# Ethernet.net
KiCad netlist of a schematic drawn in Altium Designer
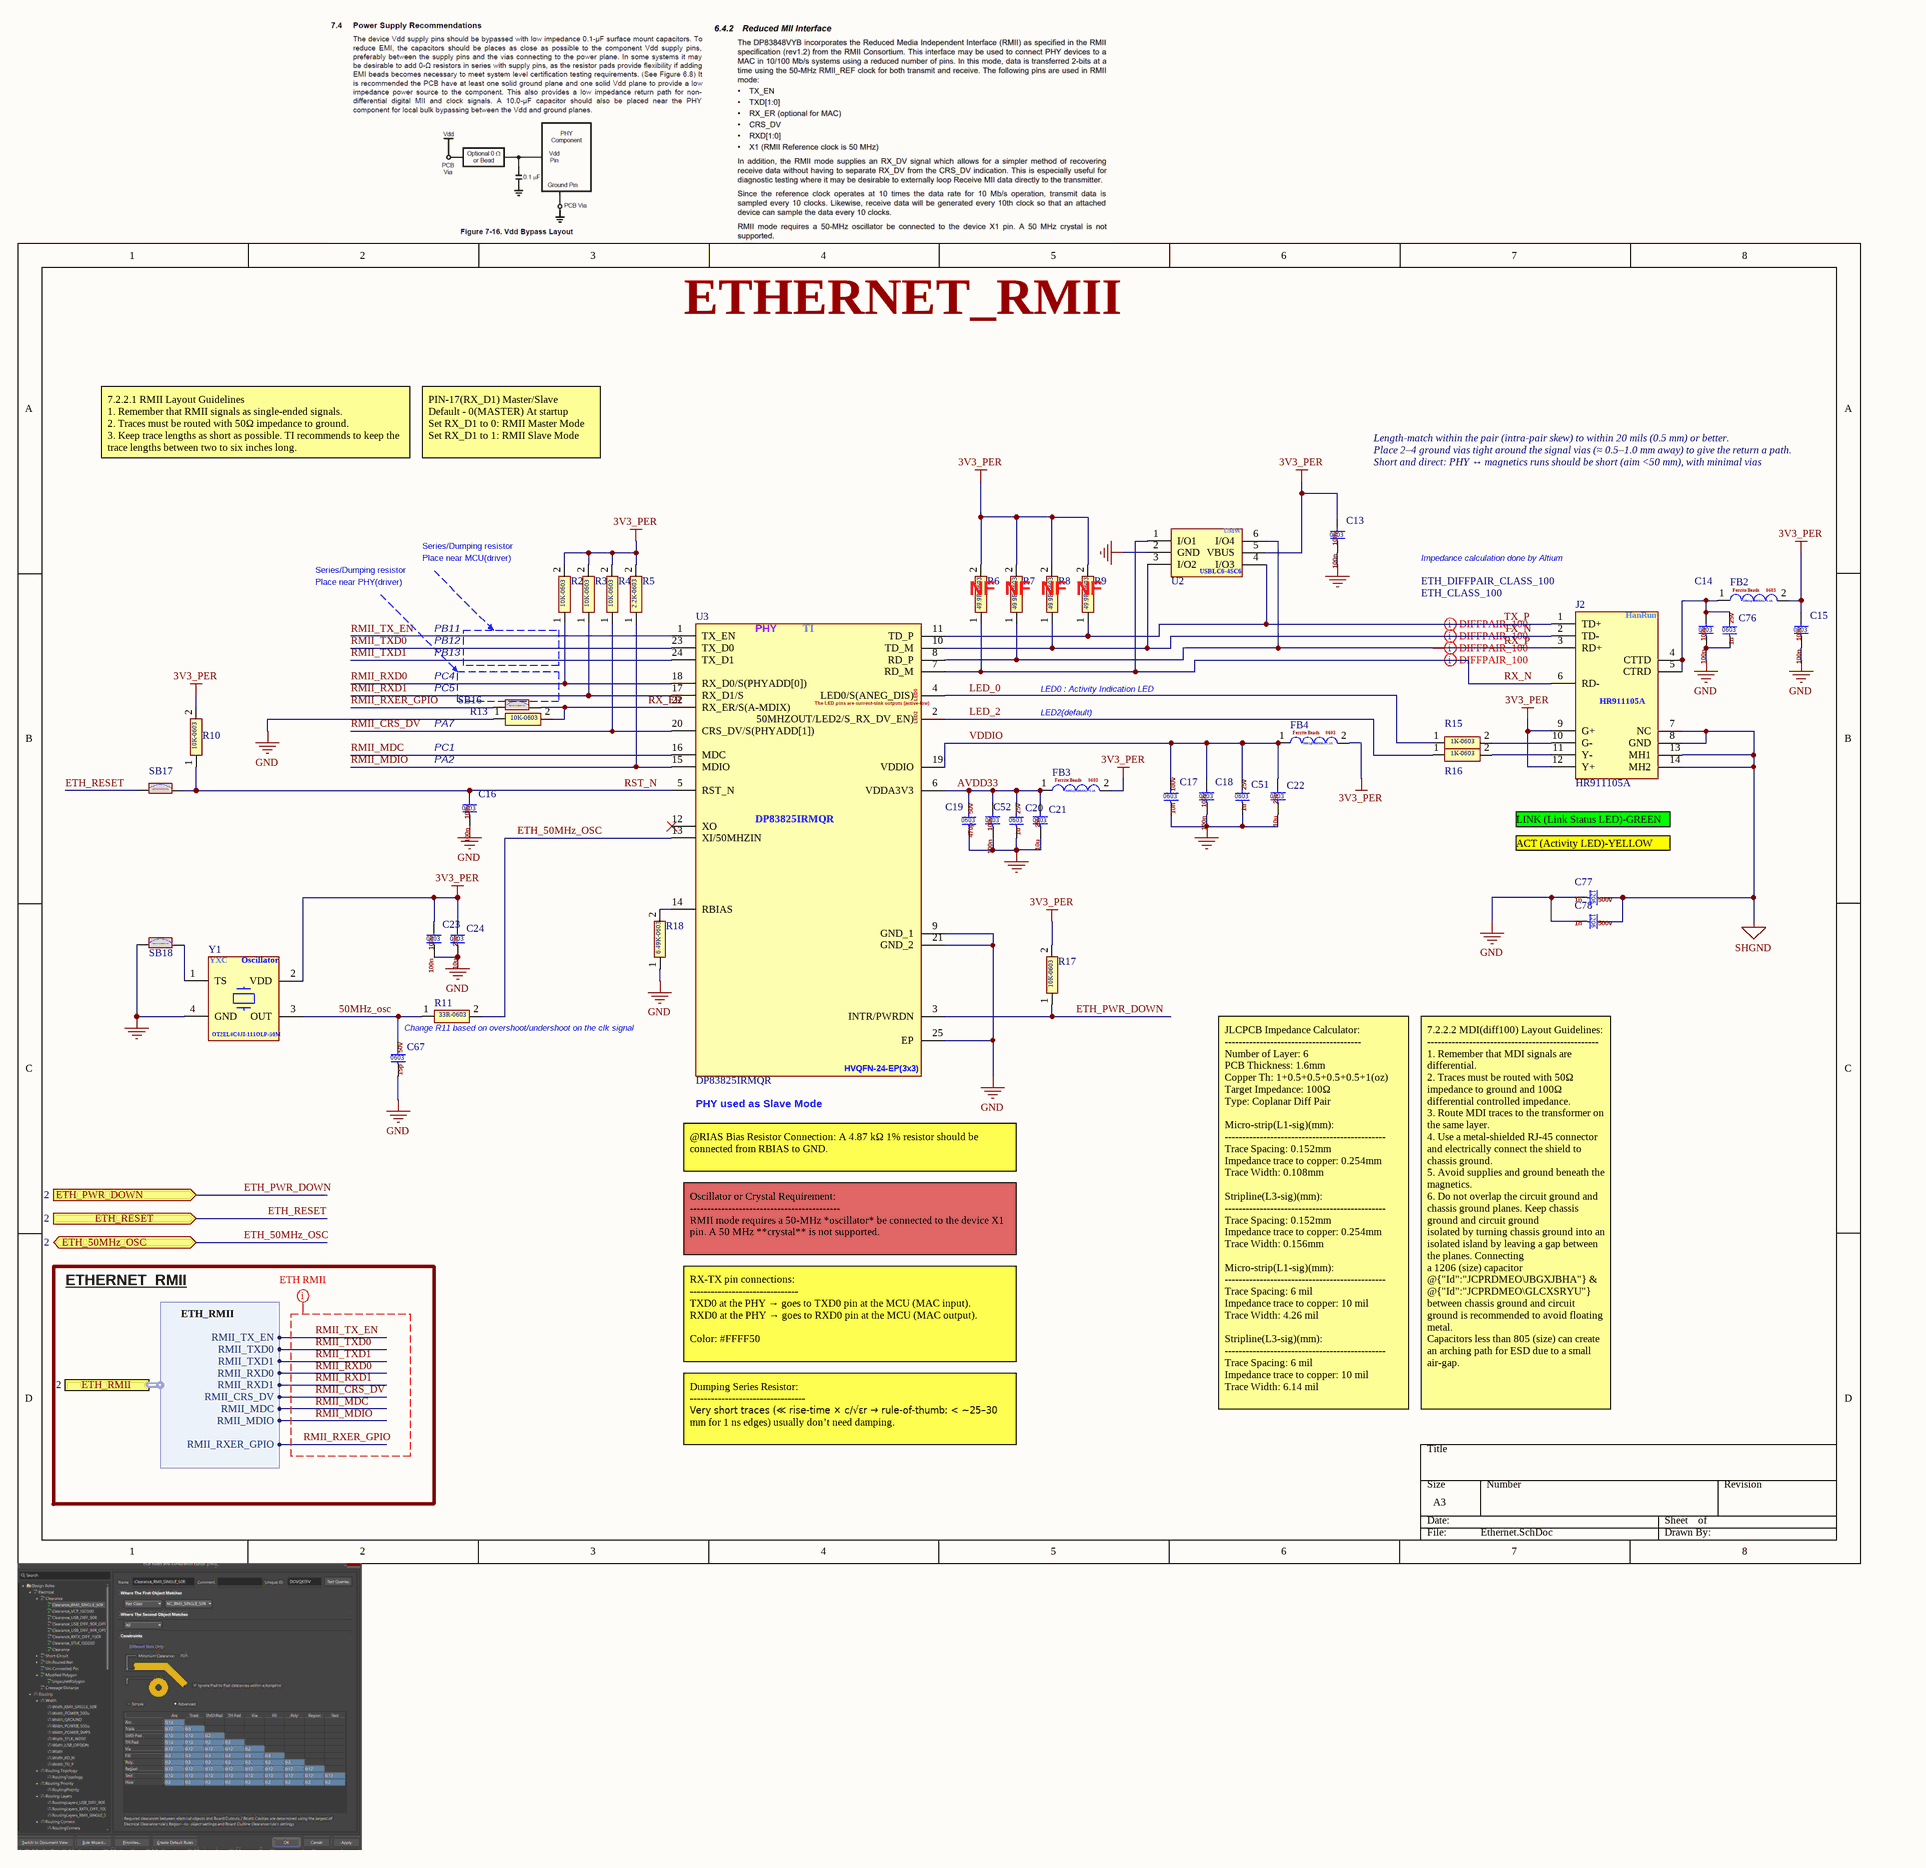
[diagram p0: Ethernet.SchDoc]

(export (version "E")
  (design (tool "Eeschema 10.0.6"))
  (components
    (comp (ref "C13")
      (value "CL10B104KC8NNNC")
      (footprint "0603-CAP")
      (description "CAP: CER 100NF 100V X7R 0603")
      (fields (field (name "LCSC PART #") "C15725"))
      (libsource (lib "Nadim Altium Lib-Univ") (part "CL10B104KC8NNNC"))
    )
    (comp (ref "C14")
      (value "CL10B104KC8NNNC")
      (footprint "0603-CAP")
      (description "CAP: CER 100NF 100V X7R 0603")
      (fields (field (name "LCSC PART #") "C15725"))
      (libsource (lib "Nadim Altium Lib-Univ") (part "CL10B104KC8NNNC"))
    )
    (comp (ref "C15")
      (value "CL10B104KC8NNNC")
      (footprint "0603-CAP")
      (description "CAP: CER 100NF 100V X7R 0603")
      (fields (field (name "LCSC PART #") "C15725"))
      (libsource (lib "Nadim Altium Lib-Univ") (part "CL10B104KC8NNNC"))
    )
    (comp (ref "C16")
      (value "CL10B104KC8NNNC")
      (footprint "0603-CAP")
      (description "CAP: CER 100NF 100V X7R 0603")
      (fields (field (name "LCSC PART #") "C15725"))
      (libsource (lib "Nadim Altium Lib-Univ") (part "CL10B104KC8NNNC"))
    )
    (comp (ref "C17")
      (value "CL10B103KC8WPNC")
      (footprint "0603-CAP")
      (description "CAP: CER 10NF 100V X7R 0603")
      (fields (field (name "LCSC PART #") "C307347"))
      (libsource (lib "Nadim Altium Lib-Univ") (part "CL10B103KC8WPNC"))
    )
    (comp (ref "C18")
      (value "CL10B104KC8NNNC")
      (footprint "0603-CAP")
      (description "CAP: CER 100NF 100V X7R 0603")
      (fields (field (name "LCSC PART #") "C15725"))
      (libsource (lib "Nadim Altium Lib-Univ") (part "CL10B104KC8NNNC"))
    )
    (comp (ref "C19")
      (value "CL10B471KB8NNNC")
      (footprint "0603-CAP")
      (description "CAP: CER 470PF 50V X7R 0603")
      (fields (field (name "LCSC PART #") "C22396"))
      (libsource (lib "Nadim Altium Lib-Univ") (part "CL10B471KB8NNNC"))
    )
    (comp (ref "C20")
      (value "CL10B105KA8NNNC")
      (footprint "0603-CAP")
      (description "CAP: CER 1UF 25V X7R 0603")
      (fields (field (name "LCSC PART #") "C29936"))
      (libsource (lib "Nadim Altium Lib-Univ") (part "CL10B105KA8NNNC"))
    )
    (comp (ref "C21")
      (value "CL10A106MA8NRNC")
      (footprint "0603-CAP")
      (description "CAP: CER 10UF 25V X5R 0603")
      (fields (field (name "LCSC PART #") "C96446"))
      (libsource (lib "Nadim Altium Lib-Univ") (part "CL10A106MA8NRNC"))
    )
    (comp (ref "C22")
      (value "CL10A106MA8NRNC")
      (footprint "0603-CAP")
      (description "CAP: CER 10UF 25V X5R 0603")
      (fields (field (name "LCSC PART #") "C96446"))
      (libsource (lib "Nadim Altium Lib-Univ") (part "CL10A106MA8NRNC"))
    )
    (comp (ref "C23")
      (value "CL10B104KC8NNNC")
      (footprint "0603-CAP")
      (description "CAP: CER 100NF 100V X7R 0603")
      (fields (field (name "LCSC PART #") "C15725"))
      (libsource (lib "Nadim Altium Lib-Univ") (part "CL10B104KC8NNNC"))
    )
    (comp (ref "C24")
      (value "CL10A106MA8NRNC")
      (footprint "0603-CAP")
      (description "CAP: CER 10UF 25V X5R 0603")
      (fields (field (name "LCSC PART #") "C96446"))
      (libsource (lib "Nadim Altium Lib-Univ") (part "CL10A106MA8NRNC"))
    )
    (comp (ref "C51")
      (value "CL10B105KA8NNNC")
      (footprint "0603-CAP")
      (description "CAP: CER 1UF 25V X7R 0603")
      (fields (field (name "LCSC PART #") "C29936"))
      (libsource (lib "Nadim Altium Lib-Univ") (part "CL10B105KA8NNNC"))
    )
    (comp (ref "C52")
      (value "CL10B104KC8NNNC")
      (footprint "0603-CAP")
      (description "CAP: CER 100NF 100V X7R 0603")
      (fields (field (name "LCSC PART #") "C15725"))
      (libsource (lib "Nadim Altium Lib-Univ") (part "CL10B104KC8NNNC"))
    )
    (comp (ref "C67")
      (value "CL10C150JB8NNNC")
      (footprint "0603-CAP")
      (description "CAP: CER 15PF 50V C0G 0603")
      (fields (field (name "LCSC PART #") "C1644"))
      (libsource (lib "Nadim Altium Lib-Univ") (part "CL10C150JB8NNNC"))
    )
    (comp (ref "C76")
      (value "CL10B105KA8NNNC")
      (footprint "0603-CAP")
      (description "CAP: CER 1UF 25V X7R 0603")
      (fields (field (name "LCSC PART #") "C29936"))
      (libsource (lib "Nadim Altium Lib-Univ") (part "CL10B105KA8NNNC"))
    )
    (comp (ref "C77")
      (value "CL31B102KGFNNNE")
      (footprint "1206-CAP")
      (description "CAP: SAFETY CER 1NF 500V X7R 1206")
      (fields (field (name "LCSC PART #") "C35216"))
      (libsource (lib "Nadim Altium Lib-Univ") (part "CL31B102KGFNNNE"))
    )
    (comp (ref "C78")
      (value "CL31B102KGFNNNE")
      (footprint "1206-CAP")
      (description "CAP: SAFETY CER 1NF 500V X7R 1206")
      (fields (field (name "LCSC PART #") "C35216"))
      (libsource (lib "Nadim Altium Lib-Univ") (part "CL31B102KGFNNNE"))
    )
    (comp (ref "FB2")
      (value "BLM18KG601SN1D")
      (footprint "Nadim Altium Lib-Univ:Ferrite Beads 0603")
      (description "Ferrite Beads: 150mΩ 600Ω@100MHz 1.3A muRata")
      (fields (field (name "LCSC PART #") "C85833"))
      (libsource (lib "Nadim Altium Lib-Univ") (part "BLM18KG601SN1D"))
    )
    (comp (ref "FB3")
      (value "BLM18KG601SN1D")
      (footprint "Nadim Altium Lib-Univ:Ferrite Beads 0603")
      (description "Ferrite Beads: 150mΩ 600Ω@100MHz 1.3A muRata")
      (fields (field (name "LCSC PART #") "C85833"))
      (libsource (lib "Nadim Altium Lib-Univ") (part "BLM18KG601SN1D"))
    )
    (comp (ref "FB4")
      (value "BLM18KG601SN1D")
      (footprint "Nadim Altium Lib-Univ:Ferrite Beads 0603")
      (description "Ferrite Beads: 150mΩ 600Ω@100MHz 1.3A muRata")
      (fields (field (name "LCSC PART #") "C85833"))
      (libsource (lib "Nadim Altium Lib-Univ") (part "BLM18KG601SN1D"))
    )
    (comp (ref "J2")
      (value "HR911105A")
      (footprint "Nadim Altium Lib-Univ:HR911105A")
      (fields (field (name "LCSC PART #") "C12074"))
      (libsource (lib "Nadim Altium Lib-Univ") (part "HR911105A"))
    )
    (comp (ref "R2")
      (value "0603WAF1002T5E")
      (footprint "0603-RES")
      (description "RES: 10K OHM 1% 100mW 0603 75V")
      (fields (field (name "LCSC PART #") "C25804"))
      (libsource (lib "Nadim Altium Lib-Univ") (part "0603WAF1002T5E"))
    )
    (comp (ref "R3")
      (value "0603WAF1002T5E")
      (footprint "0603-RES")
      (description "RES: 10K OHM 1% 100mW 0603 75V")
      (fields (field (name "LCSC PART #") "C25804"))
      (libsource (lib "Nadim Altium Lib-Univ") (part "0603WAF1002T5E"))
    )
    (comp (ref "R4")
      (value "0603WAF1002T5E")
      (footprint "0603-RES")
      (description "RES: 10K OHM 1% 100mW 0603 75V")
      (fields (field (name "LCSC PART #") "C25804"))
      (libsource (lib "Nadim Altium Lib-Univ") (part "0603WAF1002T5E"))
    )
    (comp (ref "R5")
      (value "0603WAF2201T5E")
      (footprint "0603-RES")
      (description "RES: 2.2K OHM 1% 100mW 0603 75V")
      (fields (field (name "LCSC PART #") "C4190"))
      (libsource (lib "Nadim Altium Lib-Univ") (part "0603WAF2201T5E"))
    )
    (comp (ref "R6")
      (value "0603WAF499JT5E")
      (footprint "0603-RES")
      (description "RES: 49.9 OHM 1% 100mW 0603")
      (fields (field (name "LCSC PART #") "C23185"))
      (libsource (lib "Nadim Altium Lib-Univ") (part "0603WAF499JT5E"))
    )
    (comp (ref "R7")
      (value "0603WAF499JT5E")
      (footprint "0603-RES")
      (description "RES: 49.9 OHM 1% 100mW 0603")
      (fields (field (name "LCSC PART #") "C23185"))
      (libsource (lib "Nadim Altium Lib-Univ") (part "0603WAF499JT5E"))
    )
    (comp (ref "R8")
      (value "0603WAF499JT5E")
      (footprint "0603-RES")
      (description "RES: 49.9 OHM 1% 100mW 0603")
      (fields (field (name "LCSC PART #") "C23185"))
      (libsource (lib "Nadim Altium Lib-Univ") (part "0603WAF499JT5E"))
    )
    (comp (ref "R9")
      (value "0603WAF499JT5E")
      (footprint "0603-RES")
      (description "RES: 49.9 OHM 1% 100mW 0603")
      (fields (field (name "LCSC PART #") "C23185"))
      (libsource (lib "Nadim Altium Lib-Univ") (part "0603WAF499JT5E"))
    )
    (comp (ref "R10")
      (value "0603WAF1002T5E")
      (footprint "0603-RES")
      (description "RES: 10K OHM 1% 100mW 0603 75V")
      (fields (field (name "LCSC PART #") "C25804"))
      (libsource (lib "Nadim Altium Lib-Univ") (part "0603WAF1002T5E"))
    )
    (comp (ref "R11")
      (value "0603WAF330JT5E")
      (footprint "0603-RES")
      (description "RES: 33 OHM 1% 100mW 0603 75V")
      (fields (field (name "LCSC PART #") "C23140"))
      (libsource (lib "Nadim Altium Lib-Univ") (part "0603WAF330JT5E"))
    )
    (comp (ref "R13")
      (value "0603WAF1002T5E")
      (footprint "0603-RES")
      (description "RES: 10K OHM 1% 100mW 0603 75V")
      (fields (field (name "LCSC PART #") "C25804"))
      (libsource (lib "") (part "0603WAF1002T5E_1"))
    )
    (comp (ref "R15")
      (value "0603WAF1001T5E")
      (footprint "0603-RES")
      (description "RES: 1K OHM 1% 100mW 0603 75V")
      (fields (field (name "LCSC PART #") "C21190"))
      (libsource (lib "Nadim Altium Lib-Univ") (part "0603WAF1001T5E"))
    )
    (comp (ref "R16")
      (value "0603WAF1001T5E")
      (footprint "0603-RES")
      (description "RES: 1K OHM 1% 100mW 0603 75V")
      (fields (field (name "LCSC PART #") "C21190"))
      (libsource (lib "Nadim Altium Lib-Univ") (part "0603WAF1001T5E"))
    )
    (comp (ref "R17")
      (value "0603WAF1002T5E")
      (footprint "0603-RES")
      (description "RES: 10K OHM 1% 100mW 0603 75V")
      (fields (field (name "LCSC PART #") "C25804"))
      (libsource (lib "Nadim Altium Lib-Univ") (part "0603WAF1002T5E"))
    )
    (comp (ref "R18")
      (value "0603WAF6491T5E")
      (footprint "0603-RES")
      (description "RES: 6.49K OHM 1% 100mW 0603 75V")
      (fields (field (name "LCSC PART #") "C23088"))
      (libsource (lib "Nadim Altium Lib-Univ") (part "0603WAF6491T5E"))
    )
    (comp (ref "SB16")
      (value "0603WAF0000T5E")
      (footprint "SOLDER-BRIDGE_R0603-0R")
      (description "Solder Bridge: ON SB 0603")
      (fields (field (name "LCSC PART #") "C21189"))
      (libsource (lib "Nadim Altium Lib-Univ") (part "0603WAF0000T5E"))
    )
    (comp (ref "SB17")
      (value "0603WAF0000T5E")
      (footprint "SOLDER-BRIDGE_R0603-0R")
      (description "Solder Bridge: ON SB 0603")
      (fields (field (name "LCSC PART #") "C21189"))
      (libsource (lib "Nadim Altium Lib-Univ") (part "0603WAF0000T5E"))
    )
    (comp (ref "SB18")
      (value "0603WAF0000T5E")
      (footprint "SOLDER-BRIDGE_R0603-0R")
      (description "Solder Bridge: ON SB 0603")
      (fields (field (name "LCSC PART #") "C21189"))
      (libsource (lib "Nadim Altium Lib-Univ") (part "0603WAF0000T5E"))
    )
    (comp (ref "U2")
      (value "USBLC6-4SC6")
      (footprint "SOT-23-6")
      (description "ESD: 3.5A@8/20us 13V 60W@8/20us 7.8V 5V SOT-23-6 ESD and Surge Protection (TVS/ESD) ROHS")
      (fields (field (name "LCSC PART #") "C19626383"))
      (libsource (lib "Nadim Altium Lib-Univ") (part "USBLC6-4SC6"))
    )
    (comp (ref "U3")
      (value "DP83825IRMQR")
      (footprint "Nadim Altium Lib-Univ:HVQFN-24-EP(3x3)")
      (description "PHY: Ethernet Transceiver RMII HVQFN-24-EP(3x3) Ethernet Transceivers ROHS")
      (fields (field (name "LCSC PART #") "C783599"))
      (libsource (lib "Nadim Altium Lib-Univ") (part "DP83825IRMQR"))
    )
    (comp (ref "Y1")
      (value "OT2EL4C4JI-111OLP-50M")
      (footprint "Nadim Altium Lib-Univ:SMD3225-4P")
      (description "Crystal: 1.8V~3.3V ±10ppm ±20ppm CMOS 50MHz SMD3225-4P Crystal Oscillators ROHS")
      (fields (field (name "LCSC PART #") "C5203552"))
      (libsource (lib "Nadim Altium Lib-Univ") (part "OT2EL4C4JI-111OLP-50M"))
    )
  )
  (nets
    (net (code "2") (name "/50MHz_osc") (class "Default")
      (node (ref "C67") (pin "2") (pinfunction "2_2") (pintype "passive"))
      (node (ref "R11") (pin "1") (pinfunction "1_1") (pintype "passive"))
      (node (ref "Y1") (pin "3") (pinfunction "OUT_3") (pintype "passive"))
    )
    (net (code "3") (name "/AVDD33") (class "Default")
      (node (ref "C19") (pin "2") (pinfunction "2_2") (pintype "passive"))
      (node (ref "C20") (pin "2") (pinfunction "2_2") (pintype "passive"))
      (node (ref "C21") (pin "2") (pinfunction "2_2") (pintype "passive"))
      (node (ref "C52") (pin "2") (pinfunction "2_2") (pintype "passive"))
      (node (ref "FB3") (pin "1") (pinfunction "1_1") (pintype "passive"))
      (node (ref "U3") (pin "6") (pinfunction "VDDA3V3_6") (pintype "passive"))
    )
    (net (code "4") (name "/ETH_50MHz_OSC") (class "Default")
      (node (ref "R11") (pin "2") (pinfunction "2_2") (pintype "passive"))
      (node (ref "U3") (pin "13") (pinfunction "XI/50MHZIN_13") (pintype "passive"))
    )
    (net (code "5") (name "/ETH_PWR_DOWN") (class "Default")
      (node (ref "R17") (pin "1") (pinfunction "1_1") (pintype "passive"))
      (node (ref "U3") (pin "3") (pinfunction "INTR/PWRDN_3") (pintype "passive"))
    )
    (net (code "6") (name "/ETH_RESET") (class "Default")
      (node (ref "SB17") (pin "1") (pinfunction "1_1") (pintype "passive"))
    )
    (net (code "7") (name "/LED_0") (class "Default")
      (node (ref "R15") (pin "1") (pinfunction "1_1") (pintype "passive"))
      (node (ref "U3") (pin "4") (pinfunction "LED0/S(ANEG_DIS)_4") (pintype "passive"))
    )
    (net (code "8") (name "/LED_2") (class "Default")
      (node (ref "R16") (pin "1") (pinfunction "1_1") (pintype "passive"))
      (node (ref "U3") (pin "2") (pinfunction "50MHZOUT/LED2/S_RX_DV_EN)_2") (pintype "passive"))
    )
    (net (code "9") (name "/RMII_CRS_DV") (class "Default")
      (node (ref "R4") (pin "1") (pinfunction "1_1") (pintype "passive"))
      (node (ref "U3") (pin "20") (pinfunction "CRS_DV/S(PHYADD[1])_20") (pintype "passive"))
    )
    (net (code "10") (name "/RMII_MDC") (class "Default")
      (node (ref "U3") (pin "16") (pinfunction "MDC_16") (pintype "passive"))
    )
    (net (code "11") (name "/RMII_MDIO") (class "Default")
      (node (ref "R5") (pin "1") (pinfunction "1_1") (pintype "passive"))
      (node (ref "U3") (pin "15") (pinfunction "MDIO_15") (pintype "passive"))
    )
    (net (code "12") (name "/RMII_RXD0") (class "Default")
      (node (ref "R2") (pin "1") (pinfunction "1_1") (pintype "passive"))
      (node (ref "U3") (pin "18") (pinfunction "RX_D0/S(PHYADD[0])_18") (pintype "passive"))
    )
    (net (code "13") (name "/RMII_RXD1") (class "Default")
      (node (ref "R3") (pin "1") (pinfunction "1_1") (pintype "passive"))
      (node (ref "U3") (pin "17") (pinfunction "RX_D1/S_17") (pintype "passive"))
    )
    (net (code "14") (name "/RMII_RXER_GPIO") (class "Default")
      (node (ref "SB16") (pin "1") (pinfunction "1_1") (pintype "passive"))
    )
    (net (code "15") (name "/RMII_TXD0") (class "Default")
      (node (ref "U3") (pin "23") (pinfunction "TX_D0_23") (pintype "passive"))
    )
    (net (code "16") (name "/RMII_TXD1") (class "Default")
      (node (ref "U3") (pin "24") (pinfunction "TX_D1_24") (pintype "passive"))
    )
    (net (code "17") (name "/RMII_TX_EN") (class "Default")
      (node (ref "U3") (pin "1") (pinfunction "TX_EN_1") (pintype "passive"))
    )
    (net (code "18") (name "/RST_N") (class "Default")
      (node (ref "C16") (pin "2") (pinfunction "2_2") (pintype "passive"))
      (node (ref "R10") (pin "1") (pinfunction "1_1") (pintype "passive"))
      (node (ref "SB17") (pin "2") (pinfunction "2_2") (pintype "passive"))
      (node (ref "U3") (pin "5") (pinfunction "RST_N_5") (pintype "passive"))
    )
    (net (code "19") (name "/RX_ER") (class "Default")
      (node (ref "R13") (pin "2") (pinfunction "2_2") (pintype "passive"))
      (node (ref "SB16") (pin "2") (pinfunction "2_2") (pintype "passive"))
      (node (ref "U3") (pin "22") (pinfunction "RX_ER/S(A-MDIX)_22") (pintype "passive"))
    )
    (net (code "20") (name "/RX_N") (class "Default")
      (node (ref "J2") (pin "6") (pinfunction "RD-_6") (pintype "passive"))
      (node (ref "R6") (pin "1") (pinfunction "1_1") (pintype "passive"))
      (node (ref "U2") (pin "1") (pinfunction "I/O1_1") (pintype "passive"))
      (node (ref "U3") (pin "7") (pinfunction "RD_M_7") (pintype "passive"))
    )
    (net (code "21") (name "/RX_P") (class "Default")
      (node (ref "J2") (pin "3") (pinfunction "RD+_3") (pintype "passive"))
      (node (ref "R7") (pin "1") (pinfunction "1_1") (pintype "passive"))
      (node (ref "U2") (pin "6") (pinfunction "I/O4_6") (pintype "passive"))
      (node (ref "U3") (pin "8") (pinfunction "RD_P_8") (pintype "passive"))
    )
    (net (code "22") (name "/TX_N") (class "Default")
      (node (ref "J2") (pin "2") (pinfunction "TD-_2") (pintype "passive"))
      (node (ref "R8") (pin "1") (pinfunction "1_1") (pintype "passive"))
      (node (ref "U2") (pin "3") (pinfunction "I/O2_3") (pintype "passive"))
      (node (ref "U3") (pin "10") (pinfunction "TD_M_10") (pintype "passive"))
    )
    (net (code "23") (name "/TX_P") (class "Default")
      (node (ref "J2") (pin "1") (pinfunction "TD+_1") (pintype "passive"))
      (node (ref "R9") (pin "1") (pinfunction "1_1") (pintype "passive"))
      (node (ref "U2") (pin "4") (pinfunction "I/O3_4") (pintype "passive"))
      (node (ref "U3") (pin "11") (pinfunction "TD_P_11") (pintype "passive"))
    )
    (net (code "24") (name "/VDDIO") (class "Default")
      (node (ref "C17") (pin "2") (pinfunction "2_2") (pintype "passive"))
      (node (ref "C18") (pin "2") (pinfunction "2_2") (pintype "passive"))
      (node (ref "C22") (pin "2") (pinfunction "2_2") (pintype "passive"))
      (node (ref "C51") (pin "2") (pinfunction "2_2") (pintype "passive"))
      (node (ref "FB4") (pin "1") (pinfunction "1_1") (pintype "passive"))
      (node (ref "U3") (pin "19") (pinfunction "VDDIO_19") (pintype "passive"))
    )
    (net (code "26") (name "3V3_PER") (class "Default")
      (node (ref "C13") (pin "2") (pinfunction "2_2") (pintype "passive"))
      (node (ref "C15") (pin "2") (pinfunction "2_2") (pintype "passive"))
      (node (ref "C23") (pin "2") (pinfunction "2_2") (pintype "passive"))
      (node (ref "C24") (pin "2") (pinfunction "2_2") (pintype "passive"))
      (node (ref "FB2") (pin "2") (pinfunction "2_2") (pintype "passive"))
      (node (ref "FB3") (pin "2") (pinfunction "2_2") (pintype "passive"))
      (node (ref "FB4") (pin "2") (pinfunction "2_2") (pintype "passive"))
      (node (ref "J2") (pin "12") (pinfunction "Y+_12") (pintype "passive"))
      (node (ref "J2") (pin "9") (pinfunction "G+_9") (pintype "passive"))
      (node (ref "R10") (pin "2") (pinfunction "2_2") (pintype "passive"))
      (node (ref "R17") (pin "2") (pinfunction "2_2") (pintype "passive"))
      (node (ref "R2") (pin "2") (pinfunction "2_2") (pintype "passive"))
      (node (ref "R3") (pin "2") (pinfunction "2_2") (pintype "passive"))
      (node (ref "R4") (pin "2") (pinfunction "2_2") (pintype "passive"))
      (node (ref "R5") (pin "2") (pinfunction "2_2") (pintype "passive"))
      (node (ref "R6") (pin "2") (pinfunction "2_2") (pintype "passive"))
      (node (ref "R7") (pin "2") (pinfunction "2_2") (pintype "passive"))
      (node (ref "R8") (pin "2") (pinfunction "2_2") (pintype "passive"))
      (node (ref "R9") (pin "2") (pinfunction "2_2") (pintype "passive"))
      (node (ref "U2") (pin "5") (pinfunction "VBUS_5") (pintype "passive"))
      (node (ref "Y1") (pin "2") (pinfunction "VDD_2") (pintype "passive"))
    )
    (net (code "27") (name "GND") (class "Default")
      (node (ref "C13") (pin "1") (pinfunction "1_1") (pintype "passive"))
      (node (ref "C14") (pin "1") (pinfunction "1_1") (pintype "passive"))
      (node (ref "C15") (pin "1") (pinfunction "1_1") (pintype "passive"))
      (node (ref "C16") (pin "1") (pinfunction "1_1") (pintype "passive"))
      (node (ref "C17") (pin "1") (pinfunction "1_1") (pintype "passive"))
      (node (ref "C18") (pin "1") (pinfunction "1_1") (pintype "passive"))
      (node (ref "C19") (pin "1") (pinfunction "1_1") (pintype "passive"))
      (node (ref "C20") (pin "1") (pinfunction "1_1") (pintype "passive"))
      (node (ref "C21") (pin "1") (pinfunction "1_1") (pintype "passive"))
      (node (ref "C22") (pin "1") (pinfunction "1_1") (pintype "passive"))
      (node (ref "C23") (pin "1") (pinfunction "1_1") (pintype "passive"))
      (node (ref "C24") (pin "1") (pinfunction "1_1") (pintype "passive"))
      (node (ref "C51") (pin "1") (pinfunction "1_1") (pintype "passive"))
      (node (ref "C52") (pin "1") (pinfunction "1_1") (pintype "passive"))
      (node (ref "C67") (pin "1") (pinfunction "1_1") (pintype "passive"))
      (node (ref "C76") (pin "1") (pinfunction "1_1") (pintype "passive"))
      (node (ref "C77") (pin "1") (pinfunction "1_1") (pintype "passive"))
      (node (ref "C78") (pin "1") (pinfunction "1_1") (pintype "passive"))
      (node (ref "R13") (pin "1") (pinfunction "1_1") (pintype "passive"))
      (node (ref "R18") (pin "1") (pinfunction "1_1") (pintype "passive"))
      (node (ref "SB18") (pin "1") (pinfunction "1_1") (pintype "passive"))
      (node (ref "U2") (pin "2") (pinfunction "GND_2") (pintype "passive"))
      (node (ref "U3") (pin "21") (pinfunction "GND_2_21") (pintype "passive"))
      (node (ref "U3") (pin "25") (pinfunction "EP_25") (pintype "passive"))
      (node (ref "U3") (pin "9") (pinfunction "GND_1_9") (pintype "passive"))
      (node (ref "Y1") (pin "4") (pinfunction "GND_4") (pintype "passive"))
    )
    (net (code "28") (name "Net-(J2-CTRD)") (class "Default")
      (node (ref "C14") (pin "2") (pinfunction "2_2") (pintype "passive"))
      (node (ref "C76") (pin "2") (pinfunction "2_2") (pintype "passive"))
      (node (ref "FB2") (pin "1") (pinfunction "1_1") (pintype "passive"))
      (node (ref "J2") (pin "4") (pinfunction "CTTD_4") (pintype "passive"))
      (node (ref "J2") (pin "5") (pinfunction "CTRD_5") (pintype "passive"))
    )
    (net (code "29") (name "Net-(J2-G-)") (class "Default")
      (node (ref "J2") (pin "10") (pinfunction "G-_10") (pintype "passive"))
      (node (ref "R15") (pin "2") (pinfunction "2_2") (pintype "passive"))
    )
    (net (code "30") (name "Net-(J2-Y-)") (class "Default")
      (node (ref "J2") (pin "11") (pinfunction "Y-_11") (pintype "passive"))
      (node (ref "R16") (pin "2") (pinfunction "2_2") (pintype "passive"))
    )
    (net (code "31") (name "Net-(U3-RBIAS)") (class "Default")
      (node (ref "R18") (pin "2") (pinfunction "2_2") (pintype "passive"))
      (node (ref "U3") (pin "14") (pinfunction "RBIAS_14") (pintype "passive"))
    )
    (net (code "32") (name "Net-(Y1-TS)") (class "Default")
      (node (ref "SB18") (pin "2") (pinfunction "2_2") (pintype "passive"))
      (node (ref "Y1") (pin "1") (pinfunction "TS_1") (pintype "passive"))
    )
    (net (code "33") (name "SHGND") (class "Default")
      (node (ref "C77") (pin "2") (pinfunction "2_2") (pintype "passive"))
      (node (ref "C78") (pin "2") (pinfunction "2_2") (pintype "passive"))
      (node (ref "J2") (pin "13") (pinfunction "MH1_13") (pintype "passive"))
      (node (ref "J2") (pin "14") (pinfunction "MH2_14") (pintype "passive"))
      (node (ref "J2") (pin "7") (pinfunction "NC_7") (pintype "passive"))
      (node (ref "J2") (pin "8") (pinfunction "GND_8") (pintype "passive"))
    )
    (net (code "34") (name "unconnected-(U3-XO-Pad12)") (class "Default")
      (node (ref "U3") (pin "12") (pinfunction "XO_12") (pintype "passive+no_connect"))
    )
  )
)
